# ProgramCounter.net
KiCad netlist of a schematic drawn in Altium Designer
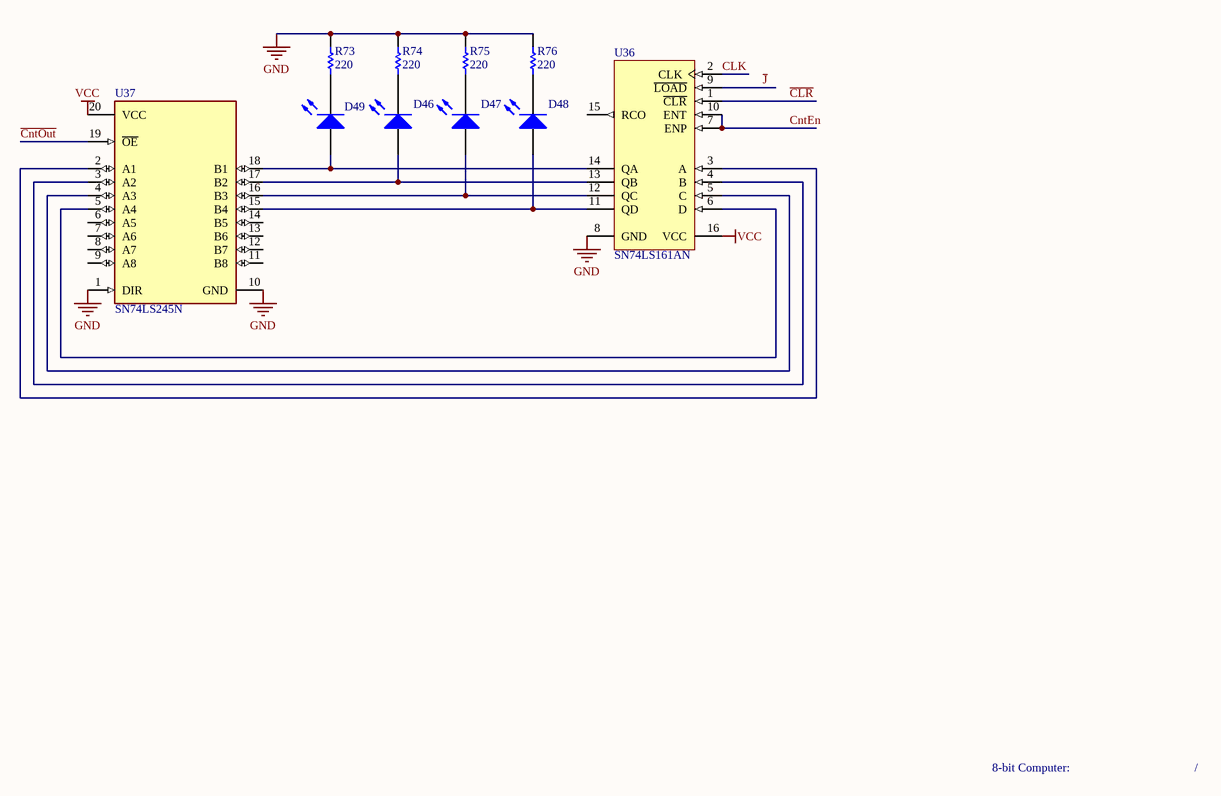
[diagram p0: ProgramCounter.SchDoc]

(export (version "E")
  (design (tool "Eeschema 10.0.6"))
  (components
    (comp (ref "D46")
      (value "Light-Emitting Diode")
      (libsource (lib "Simulation Generic Components") (part "LED"))
    )
    (comp (ref "D47")
      (value "Light-Emitting Diode")
      (libsource (lib "Simulation Generic Components") (part "LED"))
    )
    (comp (ref "D48")
      (value "Light-Emitting Diode")
      (libsource (lib "Simulation Generic Components") (part "LED"))
    )
    (comp (ref "D49")
      (value "Light-Emitting Diode")
      (libsource (lib "Simulation Generic Components") (part "LED"))
    )
    (comp (ref "R73")
      (value "220")
      (description "Resistor")
      (libsource (lib "Simulation Generic Components") (part "Resistor"))
    )
    (comp (ref "R74")
      (value "220")
      (description "Resistor")
      (libsource (lib "Simulation Generic Components") (part "Resistor"))
    )
    (comp (ref "R75")
      (value "220")
      (description "Resistor")
      (libsource (lib "Simulation Generic Components") (part "Resistor"))
    )
    (comp (ref "R76")
      (value "220")
      (description "Resistor")
      (libsource (lib "Simulation Generic Components") (part "Resistor"))
    )
    (comp (ref "U36")
      (value "SN74LS161AN")
      (footprint "N0016A")
      (description "Synchronous 4-Bit Binary Counters, N0016A, TUBE")
      (fields
        (field (name "GENERIC PART NUMBER") "SN74LS161A")
        (field (name "MANUFACTURER") "Texas Instruments")
      )
      (libsource (lib "SN74LS161AN") (part "CMP-1623-00512-2"))
    )
    (comp (ref "U37")
      (value "SN74LS245N")
      (footprint "FP-N0020A-MFG")
      (description "IC TXRX NON-INVERT 5.25V 20DIP")
      (libsource (lib "SN74LS245N") (part "CMP-1620-00419-3"))
    )
  )
  (nets
    (net (code "1") (name "/CLK") (class "Default")
      (node (ref "U36") (pin "2") (pinfunction "CLK_2") (pintype "input"))
    )
    (net (code "2") (name "/CntEn") (class "Default")
      (node (ref "U36") (pin "10") (pinfunction "ENT_10") (pintype "input"))
      (node (ref "U36") (pin "7") (pinfunction "ENP_7") (pintype "input"))
    )
    (net (code "3") (name "/~{CLR}") (class "Default")
      (node (ref "U36") (pin "1") (pinfunction "~{CLR}_1") (pintype "input"))
    )
    (net (code "4") (name "/~{CntOut}") (class "Default")
      (node (ref "U37") (pin "19") (pinfunction "~{OE}_19") (pintype "input"))
    )
    (net (code "5") (name "/~{J}") (class "Default")
      (node (ref "U36") (pin "9") (pinfunction "~{LOAD}_9") (pintype "input"))
    )
    (net (code "6") (name "GND") (class "Default")
      (node (ref "R73") (pin "2") (pinfunction "2_2") (pintype "passive"))
      (node (ref "R74") (pin "2") (pinfunction "2_2") (pintype "passive"))
      (node (ref "R75") (pin "2") (pinfunction "2_2") (pintype "passive"))
      (node (ref "R76") (pin "2") (pinfunction "2_2") (pintype "passive"))
      (node (ref "U36") (pin "8") (pinfunction "GND_8") (pintype "power_in"))
      (node (ref "U37") (pin "1") (pinfunction "DIR_1") (pintype "input"))
      (node (ref "U37") (pin "10") (pinfunction "GND_10") (pintype "power_in"))
    )
    (net (code "7") (name "Net-(D46-A)") (class "Default")
      (node (ref "D46") (pin "1") (pinfunction "A_1") (pintype "passive"))
      (node (ref "U36") (pin "13") (pinfunction "QB_13") (pintype "passive"))
      (node (ref "U37") (pin "17") (pinfunction "B2_17") (pintype "bidirectional"))
    )
    (net (code "8") (name "Net-(D46-K)") (class "Default")
      (node (ref "D46") (pin "2") (pinfunction "K_2") (pintype "passive"))
      (node (ref "R74") (pin "1") (pinfunction "1_1") (pintype "passive"))
    )
    (net (code "9") (name "Net-(D47-A)") (class "Default")
      (node (ref "D47") (pin "1") (pinfunction "A_1") (pintype "passive"))
      (node (ref "U36") (pin "12") (pinfunction "QC_12") (pintype "passive"))
      (node (ref "U37") (pin "16") (pinfunction "B3_16") (pintype "bidirectional"))
    )
    (net (code "10") (name "Net-(D47-K)") (class "Default")
      (node (ref "D47") (pin "2") (pinfunction "K_2") (pintype "passive"))
      (node (ref "R75") (pin "1") (pinfunction "1_1") (pintype "passive"))
    )
    (net (code "11") (name "Net-(D48-A)") (class "Default")
      (node (ref "D48") (pin "1") (pinfunction "A_1") (pintype "passive"))
      (node (ref "U36") (pin "11") (pinfunction "QD_11") (pintype "passive"))
      (node (ref "U37") (pin "15") (pinfunction "B4_15") (pintype "bidirectional"))
    )
    (net (code "12") (name "Net-(D48-K)") (class "Default")
      (node (ref "D48") (pin "2") (pinfunction "K_2") (pintype "passive"))
      (node (ref "R76") (pin "1") (pinfunction "1_1") (pintype "passive"))
    )
    (net (code "13") (name "Net-(D49-A)") (class "Default")
      (node (ref "D49") (pin "1") (pinfunction "A_1") (pintype "passive"))
      (node (ref "U36") (pin "14") (pinfunction "QA_14") (pintype "passive"))
      (node (ref "U37") (pin "18") (pinfunction "B1_18") (pintype "bidirectional"))
    )
    (net (code "14") (name "Net-(D49-K)") (class "Default")
      (node (ref "D49") (pin "2") (pinfunction "K_2") (pintype "passive"))
      (node (ref "R73") (pin "1") (pinfunction "1_1") (pintype "passive"))
    )
    (net (code "15") (name "Net-(U36-A)") (class "Default")
      (node (ref "U36") (pin "3") (pinfunction "A_3") (pintype "input"))
      (node (ref "U37") (pin "2") (pinfunction "A1_2") (pintype "bidirectional"))
    )
    (net (code "16") (name "Net-(U36-B)") (class "Default")
      (node (ref "U36") (pin "4") (pinfunction "B_4") (pintype "input"))
      (node (ref "U37") (pin "3") (pinfunction "A2_3") (pintype "bidirectional"))
    )
    (net (code "17") (name "Net-(U36-C)") (class "Default")
      (node (ref "U36") (pin "5") (pinfunction "C_5") (pintype "input"))
      (node (ref "U37") (pin "4") (pinfunction "A3_4") (pintype "bidirectional"))
    )
    (net (code "18") (name "Net-(U36-D)") (class "Default")
      (node (ref "U36") (pin "6") (pinfunction "D_6") (pintype "input"))
      (node (ref "U37") (pin "5") (pinfunction "A4_5") (pintype "bidirectional"))
    )
    (net (code "19") (name "VCC") (class "Default")
      (node (ref "U36") (pin "16") (pinfunction "VCC_16") (pintype "power_in"))
      (node (ref "U37") (pin "20") (pinfunction "VCC_20") (pintype "power_in"))
    )
    (net (code "20") (name "unconnected-(U36-RCO-Pad15)") (class "Default")
      (node (ref "U36") (pin "15") (pinfunction "RCO_15") (pintype "output"))
    )
    (net (code "21") (name "unconnected-(U37-A5-Pad6)") (class "Default")
      (node (ref "U37") (pin "6") (pinfunction "A5_6") (pintype "bidirectional"))
    )
    (net (code "22") (name "unconnected-(U37-A6-Pad7)") (class "Default")
      (node (ref "U37") (pin "7") (pinfunction "A6_7") (pintype "bidirectional"))
    )
    (net (code "23") (name "unconnected-(U37-A7-Pad8)") (class "Default")
      (node (ref "U37") (pin "8") (pinfunction "A7_8") (pintype "bidirectional"))
    )
    (net (code "24") (name "unconnected-(U37-A8-Pad9)") (class "Default")
      (node (ref "U37") (pin "9") (pinfunction "A8_9") (pintype "bidirectional"))
    )
    (net (code "25") (name "unconnected-(U37-B5-Pad14)") (class "Default")
      (node (ref "U37") (pin "14") (pinfunction "B5_14") (pintype "bidirectional"))
    )
    (net (code "26") (name "unconnected-(U37-B6-Pad13)") (class "Default")
      (node (ref "U37") (pin "13") (pinfunction "B6_13") (pintype "bidirectional"))
    )
    (net (code "27") (name "unconnected-(U37-B7-Pad12)") (class "Default")
      (node (ref "U37") (pin "12") (pinfunction "B7_12") (pintype "bidirectional"))
    )
    (net (code "28") (name "unconnected-(U37-B8-Pad11)") (class "Default")
      (node (ref "U37") (pin "11") (pinfunction "B8_11") (pintype "bidirectional"))
    )
  )
)
